# power_board.net
KiCad netlist of a schematic drawn in EAGLE
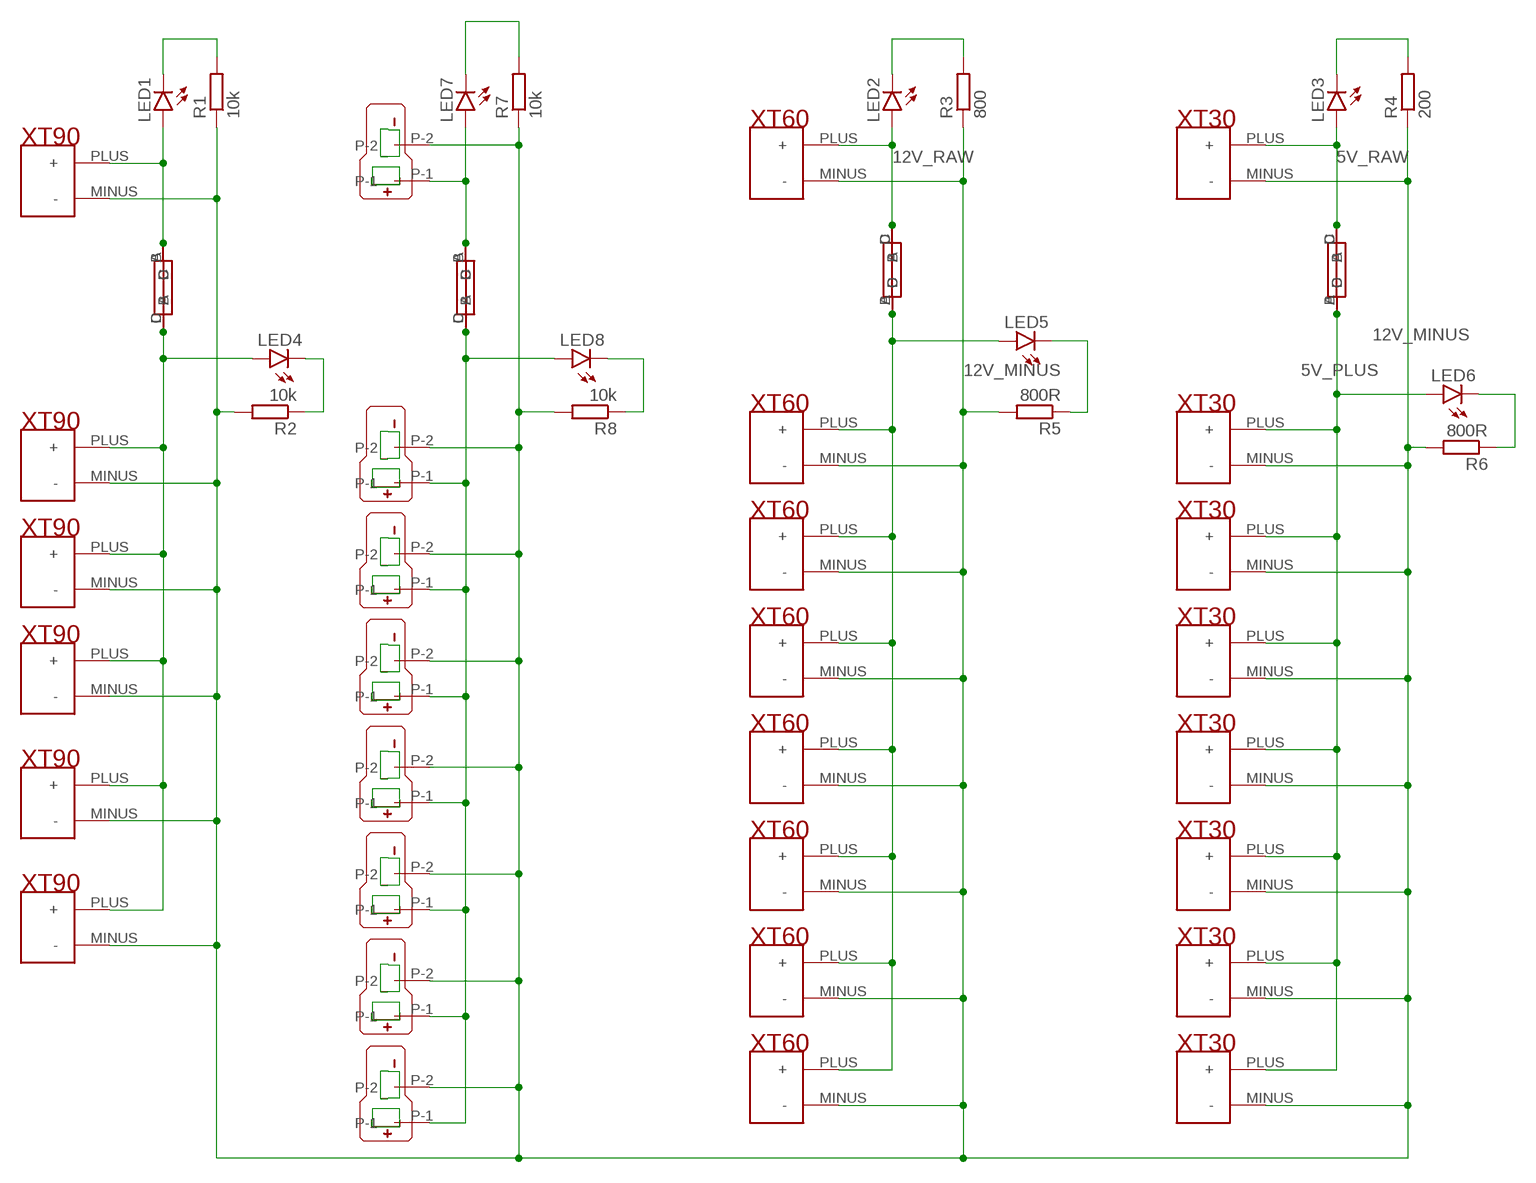
[diagram p0: schematic, sheet 1]

(export (version "E")
  (design (tool "Eeschema 10.0.6"))
  (components
    (comp (ref "LED1")
      (value "LED5MM")
      (footprint "eagle-import:LED5MM")
      (libsource (lib "eagle-import") (part "LED5MM"))
    )
    (comp (ref "LED2")
      (value "LED5MM")
      (footprint "eagle-import:LED5MM")
      (libsource (lib "eagle-import") (part "LED5MM"))
    )
    (comp (ref "LED3")
      (value "LED5MM")
      (footprint "eagle-import:LED5MM")
      (libsource (lib "eagle-import") (part "LED5MM"))
    )
    (comp (ref "LED4")
      (value "LED5MM")
      (footprint "eagle-import:LED5MM")
      (libsource (lib "eagle-import") (part "LED5MM"))
    )
    (comp (ref "LED5")
      (value "LED5MM")
      (footprint "eagle-import:LED5MM")
      (libsource (lib "eagle-import") (part "LED5MM"))
    )
    (comp (ref "LED6")
      (value "LED5MM")
      (footprint "eagle-import:LED5MM")
      (libsource (lib "eagle-import") (part "LED5MM"))
    )
    (comp (ref "LED7")
      (value "LED5MM")
      (footprint "eagle-import:LED5MM")
      (libsource (lib "eagle-import") (part "LED5MM"))
    )
    (comp (ref "LED8")
      (value "LED5MM")
      (footprint "eagle-import:LED5MM")
      (libsource (lib "eagle-import") (part "LED5MM"))
    )
    (comp (ref "R1")
      (value "10k")
      (footprint "eagle-import:M1206")
      (libsource (lib "eagle-import") (part "R-EU_M1206"))
    )
    (comp (ref "R2")
      (value "10k")
      (footprint "eagle-import:M1206")
      (libsource (lib "eagle-import") (part "R-EU_M1206"))
    )
    (comp (ref "R3")
      (value "800")
      (footprint "eagle-import:M1206")
      (libsource (lib "eagle-import") (part "R-EU_M1206"))
    )
    (comp (ref "R4")
      (value "200")
      (footprint "eagle-import:M1206")
      (libsource (lib "eagle-import") (part "R-EU_M1206"))
    )
    (comp (ref "R5")
      (value "800R")
      (footprint "eagle-import:M1206")
      (libsource (lib "eagle-import") (part "R-EU_M1206"))
    )
    (comp (ref "R6")
      (value "800R")
      (footprint "eagle-import:M1206")
      (libsource (lib "eagle-import") (part "R-EU_M1206"))
    )
    (comp (ref "R7")
      (value "10k")
      (footprint "eagle-import:M1206")
      (libsource (lib "eagle-import") (part "R-EU_M1206"))
    )
    (comp (ref "R8")
      (value "10k")
      (footprint "eagle-import:M1206")
      (libsource (lib "eagle-import") (part "R-EU_M1206"))
    )
    (comp (ref "U$1")
      (value "XT90")
      (footprint "eagle-import:XT90_FOOTPRINT")
      (libsource (lib "eagle-import") (part "XT90"))
    )
    (comp (ref "U$2")
      (value "XT90")
      (footprint "eagle-import:XT90_FOOTPRINT")
      (libsource (lib "eagle-import") (part "XT90"))
    )
    (comp (ref "U$3")
      (value "XT90")
      (footprint "eagle-import:XT90_FOOTPRINT")
      (libsource (lib "eagle-import") (part "XT90"))
    )
    (comp (ref "U$4")
      (value "XT90")
      (footprint "eagle-import:XT90_FOOTPRINT")
      (libsource (lib "eagle-import") (part "XT90"))
    )
    (comp (ref "U$5")
      (value "XT60")
      (footprint "eagle-import:XT60_FOOTPRINT")
      (libsource (lib "eagle-import") (part "XT60"))
    )
    (comp (ref "U$6")
      (value "XT60")
      (footprint "eagle-import:XT60_FOOTPRINT")
      (libsource (lib "eagle-import") (part "XT60"))
    )
    (comp (ref "U$7")
      (value "XT60")
      (footprint "eagle-import:XT60_FOOTPRINT")
      (libsource (lib "eagle-import") (part "XT60"))
    )
    (comp (ref "U$8")
      (value "XT60")
      (footprint "eagle-import:XT60_FOOTPRINT")
      (libsource (lib "eagle-import") (part "XT60"))
    )
    (comp (ref "U$9")
      (value "XT60")
      (footprint "eagle-import:XT60_FOOTPRINT")
      (libsource (lib "eagle-import") (part "XT60"))
    )
    (comp (ref "U$10")
      (value "XT60")
      (footprint "eagle-import:XT60_FOOTPRINT")
      (libsource (lib "eagle-import") (part "XT60"))
    )
    (comp (ref "U$11")
      (value "XT60")
      (footprint "eagle-import:XT60_FOOTPRINT")
      (libsource (lib "eagle-import") (part "XT60"))
    )
    (comp (ref "U$12")
      (value "XT60")
      (footprint "eagle-import:XT60_FOOTPRINT")
      (libsource (lib "eagle-import") (part "XT60"))
    )
    (comp (ref "U$13")
      (value "XT30")
      (footprint "eagle-import:XT30_FOOTPRINT")
      (libsource (lib "eagle-import") (part "XT30"))
    )
    (comp (ref "U$14")
      (value "XT30")
      (footprint "eagle-import:XT30_FOOTPRINT")
      (libsource (lib "eagle-import") (part "XT30"))
    )
    (comp (ref "U$15")
      (value "XT30")
      (footprint "eagle-import:XT30_FOOTPRINT")
      (libsource (lib "eagle-import") (part "XT30"))
    )
    (comp (ref "U$16")
      (value "XT30")
      (footprint "eagle-import:XT30_FOOTPRINT")
      (libsource (lib "eagle-import") (part "XT30"))
    )
    (comp (ref "U$17")
      (value "XT30")
      (footprint "eagle-import:XT30_FOOTPRINT")
      (libsource (lib "eagle-import") (part "XT30"))
    )
    (comp (ref "U$18")
      (value "XT30")
      (footprint "eagle-import:XT30_FOOTPRINT")
      (libsource (lib "eagle-import") (part "XT30"))
    )
    (comp (ref "U$19")
      (value "XT30")
      (footprint "eagle-import:XT30_FOOTPRINT")
      (libsource (lib "eagle-import") (part "XT30"))
    )
    (comp (ref "U$20")
      (value "XT30")
      (footprint "eagle-import:XT30_FOOTPRINT")
      (libsource (lib "eagle-import") (part "XT30"))
    )
    (comp (ref "U$21")
      (value "AUTOFUSE")
      (footprint "eagle-import:AUTOFUSE_HOLDER")
      (libsource (lib "eagle-import") (part "AUTOFUSE"))
    )
    (comp (ref "U$22")
      (value "AUTOFUSE")
      (footprint "eagle-import:AUTOFUSE_HOLDER")
      (libsource (lib "eagle-import") (part "AUTOFUSE"))
    )
    (comp (ref "U$23")
      (value "AUTOFUSE")
      (footprint "eagle-import:AUTOFUSE_HOLDER")
      (libsource (lib "eagle-import") (part "AUTOFUSE"))
    )
    (comp (ref "U$24")
      (value "XT90")
      (footprint "eagle-import:XT90_FOOTPRINT")
      (libsource (lib "eagle-import") (part "XT90"))
    )
    (comp (ref "U$25")
      (value "T-PLUG_CONNECTOR")
      (footprint "eagle-import:T_PLUG_CONNECTOR")
      (libsource (lib "eagle-import") (part "T-PLUG_CONNECTOR"))
    )
    (comp (ref "U$26")
      (value "T-PLUG_CONNECTOR")
      (footprint "eagle-import:T_PLUG_CONNECTOR")
      (libsource (lib "eagle-import") (part "T-PLUG_CONNECTOR"))
    )
    (comp (ref "U$27")
      (value "T-PLUG_CONNECTOR")
      (footprint "eagle-import:T_PLUG_CONNECTOR")
      (libsource (lib "eagle-import") (part "T-PLUG_CONNECTOR"))
    )
    (comp (ref "U$28")
      (value "T-PLUG_CONNECTOR")
      (footprint "eagle-import:T_PLUG_CONNECTOR")
      (libsource (lib "eagle-import") (part "T-PLUG_CONNECTOR"))
    )
    (comp (ref "U$29")
      (value "T-PLUG_CONNECTOR")
      (footprint "eagle-import:T_PLUG_CONNECTOR")
      (libsource (lib "eagle-import") (part "T-PLUG_CONNECTOR"))
    )
    (comp (ref "U$30")
      (value "AUTOFUSE")
      (footprint "eagle-import:AUTOFUSE_HOLDER")
      (libsource (lib "eagle-import") (part "AUTOFUSE"))
    )
    (comp (ref "U$31")
      (value "T-PLUG_CONNECTOR")
      (footprint "eagle-import:T_PLUG_CONNECTOR")
      (libsource (lib "eagle-import") (part "T-PLUG_CONNECTOR"))
    )
    (comp (ref "U$32")
      (value "T-PLUG_CONNECTOR")
      (footprint "eagle-import:T_PLUG_CONNECTOR")
      (libsource (lib "eagle-import") (part "T-PLUG_CONNECTOR"))
    )
    (comp (ref "U$33")
      (value "T-PLUG_CONNECTOR")
      (footprint "eagle-import:T_PLUG_CONNECTOR")
      (libsource (lib "eagle-import") (part "T-PLUG_CONNECTOR"))
    )
    (comp (ref "U$34")
      (value "XT90")
      (footprint "eagle-import:XT90_FOOTPRINT")
      (libsource (lib "eagle-import") (part "XT90"))
    )
  )
  (nets
    (net (code "1") (name "/5V_PLUS") (class "Default")
      (node (ref "LED6") (pin "A") (pinfunction "A_A") (pintype "passive"))
      (node (ref "U$14") (pin "PLUS") (pinfunction "+_PLUS") (pintype "bidirectional"))
      (node (ref "U$15") (pin "PLUS") (pinfunction "+_PLUS") (pintype "bidirectional"))
      (node (ref "U$16") (pin "PLUS") (pinfunction "+_PLUS") (pintype "bidirectional"))
      (node (ref "U$17") (pin "PLUS") (pinfunction "+_PLUS") (pintype "bidirectional"))
      (node (ref "U$18") (pin "PLUS") (pinfunction "+_PLUS") (pintype "bidirectional"))
      (node (ref "U$19") (pin "PLUS") (pinfunction "+_PLUS") (pintype "bidirectional"))
      (node (ref "U$20") (pin "PLUS") (pinfunction "+_PLUS") (pintype "bidirectional"))
      (node (ref "U$23") (pin "A") (pinfunction "A_A") (pintype "bidirectional"))
      (node (ref "U$23") (pin "B") (pinfunction "B_B") (pintype "bidirectional"))
    )
    (net (code "2") (name "/5V_RAW") (class "Default")
      (node (ref "LED3") (pin "A") (pinfunction "A_A") (pintype "passive"))
      (node (ref "U$13") (pin "PLUS") (pinfunction "+_PLUS") (pintype "bidirectional"))
      (node (ref "U$23") (pin "C") (pinfunction "C_C") (pintype "bidirectional"))
      (node (ref "U$23") (pin "D") (pinfunction "D_D") (pintype "bidirectional"))
    )
    (net (code "3") (name "/12V_MINUS") (class "Default")
      (node (ref "R1") (pin "1") (pinfunction "1_1") (pintype "passive"))
      (node (ref "R2") (pin "2") (pinfunction "2_2") (pintype "passive"))
      (node (ref "R3") (pin "1") (pinfunction "1_1") (pintype "passive"))
      (node (ref "R4") (pin "1") (pinfunction "1_1") (pintype "passive"))
      (node (ref "R5") (pin "2") (pinfunction "2_2") (pintype "passive"))
      (node (ref "R6") (pin "2") (pinfunction "2_2") (pintype "passive"))
      (node (ref "R7") (pin "1") (pinfunction "1_1") (pintype "passive"))
      (node (ref "R8") (pin "2") (pinfunction "2_2") (pintype "passive"))
      (node (ref "U$1") (pin "MINUS") (pinfunction "-_MINUS") (pintype "bidirectional"))
      (node (ref "U$10") (pin "MINUS") (pinfunction "-_MINUS") (pintype "bidirectional"))
      (node (ref "U$11") (pin "MINUS") (pinfunction "-_MINUS") (pintype "bidirectional"))
      (node (ref "U$12") (pin "MINUS") (pinfunction "-_MINUS") (pintype "bidirectional"))
      (node (ref "U$13") (pin "MINUS") (pinfunction "-_MINUS") (pintype "bidirectional"))
      (node (ref "U$14") (pin "MINUS") (pinfunction "-_MINUS") (pintype "bidirectional"))
      (node (ref "U$15") (pin "MINUS") (pinfunction "-_MINUS") (pintype "bidirectional"))
      (node (ref "U$16") (pin "MINUS") (pinfunction "-_MINUS") (pintype "bidirectional"))
      (node (ref "U$17") (pin "MINUS") (pinfunction "-_MINUS") (pintype "bidirectional"))
      (node (ref "U$18") (pin "MINUS") (pinfunction "-_MINUS") (pintype "bidirectional"))
      (node (ref "U$19") (pin "MINUS") (pinfunction "-_MINUS") (pintype "bidirectional"))
      (node (ref "U$2") (pin "MINUS") (pinfunction "-_MINUS") (pintype "bidirectional"))
      (node (ref "U$20") (pin "MINUS") (pinfunction "-_MINUS") (pintype "bidirectional"))
      (node (ref "U$24") (pin "MINUS") (pinfunction "-_MINUS") (pintype "bidirectional"))
      (node (ref "U$25") (pin "P-2") (pinfunction "P-2_P-2") (pintype "passive"))
      (node (ref "U$26") (pin "P-2") (pinfunction "P-2_P-2") (pintype "passive"))
      (node (ref "U$27") (pin "P-2") (pinfunction "P-2_P-2") (pintype "passive"))
      (node (ref "U$28") (pin "P-2") (pinfunction "P-2_P-2") (pintype "passive"))
      (node (ref "U$29") (pin "P-2") (pinfunction "P-2_P-2") (pintype "passive"))
      (node (ref "U$3") (pin "MINUS") (pinfunction "-_MINUS") (pintype "bidirectional"))
      (node (ref "U$31") (pin "P-2") (pinfunction "P-2_P-2") (pintype "passive"))
      (node (ref "U$32") (pin "P-2") (pinfunction "P-2_P-2") (pintype "passive"))
      (node (ref "U$33") (pin "P-2") (pinfunction "P-2_P-2") (pintype "passive"))
      (node (ref "U$34") (pin "MINUS") (pinfunction "-_MINUS") (pintype "bidirectional"))
      (node (ref "U$4") (pin "MINUS") (pinfunction "-_MINUS") (pintype "bidirectional"))
      (node (ref "U$5") (pin "MINUS") (pinfunction "-_MINUS") (pintype "bidirectional"))
      (node (ref "U$6") (pin "MINUS") (pinfunction "-_MINUS") (pintype "bidirectional"))
      (node (ref "U$7") (pin "MINUS") (pinfunction "-_MINUS") (pintype "bidirectional"))
      (node (ref "U$8") (pin "MINUS") (pinfunction "-_MINUS") (pintype "bidirectional"))
      (node (ref "U$9") (pin "MINUS") (pinfunction "-_MINUS") (pintype "bidirectional"))
    )
    (net (code "4") (name "/12V_RAW") (class "Default")
      (node (ref "LED2") (pin "A") (pinfunction "A_A") (pintype "passive"))
      (node (ref "U$22") (pin "C") (pinfunction "C_C") (pintype "bidirectional"))
      (node (ref "U$22") (pin "D") (pinfunction "D_D") (pintype "bidirectional"))
      (node (ref "U$5") (pin "PLUS") (pinfunction "+_PLUS") (pintype "bidirectional"))
    )
    (net (code "5") (name "Net-(LED1-C)") (class "Default")
      (node (ref "LED1") (pin "K") (pinfunction "C_K") (pintype "passive"))
      (node (ref "R1") (pin "2") (pinfunction "2_2") (pintype "passive"))
    )
    (net (code "6") (name "Net-(LED2-C)") (class "Default")
      (node (ref "LED2") (pin "K") (pinfunction "C_K") (pintype "passive"))
      (node (ref "R3") (pin "2") (pinfunction "2_2") (pintype "passive"))
    )
    (net (code "7") (name "Net-(LED3-C)") (class "Default")
      (node (ref "LED3") (pin "K") (pinfunction "C_K") (pintype "passive"))
      (node (ref "R4") (pin "2") (pinfunction "2_2") (pintype "passive"))
    )
    (net (code "8") (name "Net-(LED4-C)") (class "Default")
      (node (ref "LED4") (pin "K") (pinfunction "C_K") (pintype "passive"))
      (node (ref "R2") (pin "1") (pinfunction "1_1") (pintype "passive"))
    )
    (net (code "9") (name "Net-(LED5-C)") (class "Default")
      (node (ref "LED5") (pin "K") (pinfunction "C_K") (pintype "passive"))
      (node (ref "R5") (pin "1") (pinfunction "1_1") (pintype "passive"))
    )
    (net (code "10") (name "Net-(LED6-C)") (class "Default")
      (node (ref "LED6") (pin "K") (pinfunction "C_K") (pintype "passive"))
      (node (ref "R6") (pin "1") (pinfunction "1_1") (pintype "passive"))
    )
    (net (code "11") (name "Net-(LED7-C)") (class "Default")
      (node (ref "LED7") (pin "K") (pinfunction "C_K") (pintype "passive"))
      (node (ref "R7") (pin "2") (pinfunction "2_2") (pintype "passive"))
    )
    (net (code "12") (name "Net-(LED7-PadA)") (class "Default")
      (node (ref "LED7") (pin "A") (pinfunction "A_A") (pintype "passive"))
      (node (ref "U$25") (pin "P-1") (pinfunction "P-1_P-1") (pintype "passive"))
      (node (ref "U$30") (pin "A") (pinfunction "A_A") (pintype "bidirectional"))
      (node (ref "U$30") (pin "B") (pinfunction "B_B") (pintype "bidirectional"))
    )
    (net (code "13") (name "Net-(LED8-C)") (class "Default")
      (node (ref "LED8") (pin "K") (pinfunction "C_K") (pintype "passive"))
      (node (ref "R8") (pin "1") (pinfunction "1_1") (pintype "passive"))
    )
    (net (code "14") (name "Net-(LED8-PadA)") (class "Default")
      (node (ref "LED8") (pin "A") (pinfunction "A_A") (pintype "passive"))
      (node (ref "U$26") (pin "P-1") (pinfunction "P-1_P-1") (pintype "passive"))
      (node (ref "U$27") (pin "P-1") (pinfunction "P-1_P-1") (pintype "passive"))
      (node (ref "U$28") (pin "P-1") (pinfunction "P-1_P-1") (pintype "passive"))
      (node (ref "U$29") (pin "P-1") (pinfunction "P-1_P-1") (pintype "passive"))
      (node (ref "U$30") (pin "C") (pinfunction "C_C") (pintype "bidirectional"))
      (node (ref "U$30") (pin "D") (pinfunction "D_D") (pintype "bidirectional"))
      (node (ref "U$31") (pin "P-1") (pinfunction "P-1_P-1") (pintype "passive"))
      (node (ref "U$32") (pin "P-1") (pinfunction "P-1_P-1") (pintype "passive"))
      (node (ref "U$33") (pin "P-1") (pinfunction "P-1_P-1") (pintype "passive"))
    )
    (net (code "15") (name "Net-(U$1-+)") (class "Default")
      (node (ref "LED1") (pin "A") (pinfunction "A_A") (pintype "passive"))
      (node (ref "U$1") (pin "PLUS") (pinfunction "+_PLUS") (pintype "bidirectional"))
      (node (ref "U$21") (pin "A") (pinfunction "A_A") (pintype "bidirectional"))
      (node (ref "U$21") (pin "B") (pinfunction "B_B") (pintype "bidirectional"))
    )
    (net (code "16") (name "Net-(U$2-+)") (class "Default")
      (node (ref "LED4") (pin "A") (pinfunction "A_A") (pintype "passive"))
      (node (ref "U$2") (pin "PLUS") (pinfunction "+_PLUS") (pintype "bidirectional"))
      (node (ref "U$21") (pin "C") (pinfunction "C_C") (pintype "bidirectional"))
      (node (ref "U$21") (pin "D") (pinfunction "D_D") (pintype "bidirectional"))
      (node (ref "U$24") (pin "PLUS") (pinfunction "+_PLUS") (pintype "bidirectional"))
      (node (ref "U$3") (pin "PLUS") (pinfunction "+_PLUS") (pintype "bidirectional"))
      (node (ref "U$34") (pin "PLUS") (pinfunction "+_PLUS") (pintype "bidirectional"))
      (node (ref "U$4") (pin "PLUS") (pinfunction "+_PLUS") (pintype "bidirectional"))
    )
    (net (code "17") (name "Net-(U$10-+)") (class "Default")
      (node (ref "LED5") (pin "A") (pinfunction "A_A") (pintype "passive"))
      (node (ref "U$10") (pin "PLUS") (pinfunction "+_PLUS") (pintype "bidirectional"))
      (node (ref "U$11") (pin "PLUS") (pinfunction "+_PLUS") (pintype "bidirectional"))
      (node (ref "U$12") (pin "PLUS") (pinfunction "+_PLUS") (pintype "bidirectional"))
      (node (ref "U$22") (pin "A") (pinfunction "A_A") (pintype "bidirectional"))
      (node (ref "U$22") (pin "B") (pinfunction "B_B") (pintype "bidirectional"))
      (node (ref "U$6") (pin "PLUS") (pinfunction "+_PLUS") (pintype "bidirectional"))
      (node (ref "U$7") (pin "PLUS") (pinfunction "+_PLUS") (pintype "bidirectional"))
      (node (ref "U$8") (pin "PLUS") (pinfunction "+_PLUS") (pintype "bidirectional"))
      (node (ref "U$9") (pin "PLUS") (pinfunction "+_PLUS") (pintype "bidirectional"))
    )
  )
)
